# Kay_Tremolo.net
KiCad netlist of a schematic drawn in Altium Designer
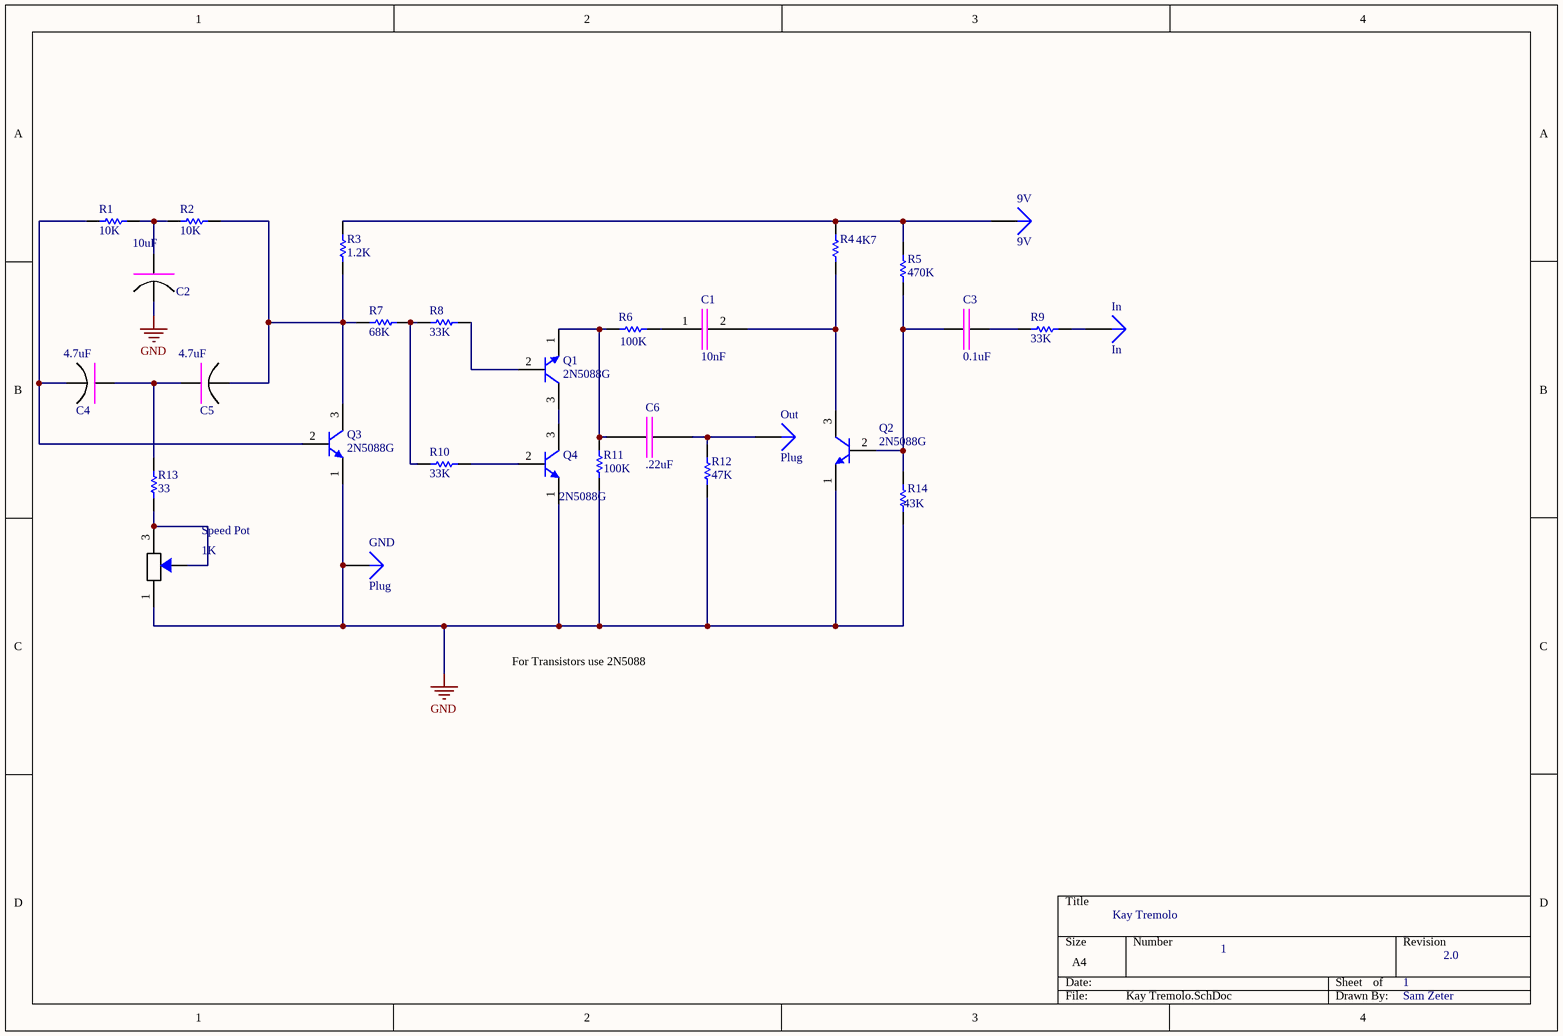
[diagram p0: Kay Tremolo.SchDoc]

(export (version "E")
  (design (tool "Eeschema 10.0.6"))
  (components
    (comp (ref "9V")
      (value "9V")
      (footprint "PIN1")
      (description "Plug")
      (fields (field (name "PUBLISHER") "Altium Limited"))
      (libsource (lib "Miscellaneous Connectors") (part "Plug"))
    )
    (comp (ref "C1")
      (value "10nF")
      (footprint "CapCer 2.5")
      (description "Ceramic Capactiro 2.5mm spaced leads")
      (libsource (lib "ZETER_Sch_Lib") (part "CapCer 2.5mm"))
    )
    (comp (ref "C2")
      (value "10uF")
      (footprint "CapElec 2")
      (description "2mm Lead Spaced Electro Cap")
      (libsource (lib "ZETER_Sch_Lib") (part "CapElec 2mm"))
    )
    (comp (ref "C3")
      (value "0.1uF")
      (footprint "CapCer 5")
      (description "5mm Spaced Ceramic Capacitor Leads")
      (libsource (lib "ZETER_Sch_Lib") (part "CapCer 5mm"))
    )
    (comp (ref "C4")
      (value "4.7uF")
      (footprint "CapElec 2")
      (description "2mm Lead Spaced Electro Cap")
      (libsource (lib "ZETER_Sch_Lib") (part "CapElec 2mm"))
    )
    (comp (ref "C5")
      (value "4.7uF")
      (footprint "CapElec 2")
      (description "2mm Lead Spaced Electro Cap")
      (libsource (lib "ZETER_Sch_Lib") (part "CapElec 2mm"))
    )
    (comp (ref "C6")
      (value ".22uF")
      (footprint "CapCer 5")
      (description "5mm Spaced Ceramic Capacitor Leads")
      (libsource (lib "") (part "CapCer 5mm_1"))
    )
    (comp (ref "GND")
      (value "Plug")
      (footprint "PIN1")
      (fields (field (name "PUBLISHER") "Altium Limited"))
      (libsource (lib "Miscellaneous Connectors") (part "Plug"))
    )
    (comp (ref "In")
      (value "In")
      (footprint "PIN1")
      (description "Plug")
      (fields (field (name "PUBLISHER") "Altium Limited"))
      (libsource (lib "Miscellaneous Connectors") (part "Plug"))
    )
    (comp (ref "Out")
      (value "Plug")
      (footprint "PIN1")
      (fields (field (name "PUBLISHER") "Altium Limited"))
      (libsource (lib "Miscellaneous Connectors") (part "Plug"))
    )
    (comp (ref "Q1")
      (value "2N5088G")
      (footprint "ONSC-TO-92-3-29-11")
      (description "Amplifier Transistor, NPN Silicon, 3-Pin TO-92, Pb-Free, Bulk Box")
      (fields (field (name "MANUFACTURER") "On Semiconductor"))
      (libsource (lib "ON Semi General Purpose Transistors") (part "2N5088G"))
    )
    (comp (ref "Q2")
      (value "2N5088G")
      (footprint "ONSC-TO-92-3-29-11")
      (description "Amplifier Transistor, NPN Silicon, 3-Pin TO-92, Pb-Free, Bulk Box")
      (fields (field (name "MANUFACTURER") "On Semiconductor"))
      (libsource (lib "ON Semi General Purpose Transistors") (part "2N5088G"))
    )
    (comp (ref "Q3")
      (value "2N5088G")
      (footprint "ONSC-TO-92-3-29-11")
      (description "Amplifier Transistor, NPN Silicon, 3-Pin TO-92, Pb-Free, Bulk Box")
      (fields (field (name "MANUFACTURER") "On Semiconductor"))
      (libsource (lib "ON Semi General Purpose Transistors") (part "2N5088G"))
    )
    (comp (ref "Q4")
      (value "2N5088G")
      (footprint "ONSC-TO-92-3-29-11")
      (description "Amplifier Transistor, NPN Silicon, 3-Pin TO-92, Pb-Free, Bulk Box")
      (fields (field (name "MANUFACTURER") "On Semiconductor"))
      (libsource (lib "ON Semi General Purpose Transistors") (part "2N5088G"))
    )
    (comp (ref "R1")
      (value "10K")
      (footprint "Axial 0.4")
      (description "TH Resistor 1/4 WATT")
      (fields (field (name "PUBLISHER") "Altium Limited"))
      (libsource (lib "ZETER_Sch_Lib") (part "Res 0.4"))
    )
    (comp (ref "R2")
      (value "10K")
      (footprint "Axial 0.4")
      (description "TH Resistor 1/4 WATT")
      (fields (field (name "PUBLISHER") "Altium Limited"))
      (libsource (lib "ZETER_Sch_Lib") (part "Res 0.4"))
    )
    (comp (ref "R3")
      (value "1.2K")
      (footprint "Axial 0.4")
      (description "TH Resistor 1/4 WATT")
      (fields (field (name "PUBLISHER") "Altium Limited"))
      (libsource (lib "ZETER_Sch_Lib") (part "Res 0.4"))
    )
    (comp (ref "R4")
      (value "4K7")
      (footprint "Axial 0.4")
      (description "TH Resistor 1/4 WATT")
      (fields (field (name "PUBLISHER") "Altium Limited"))
      (libsource (lib "ZETER_Sch_Lib") (part "Res 0.4"))
    )
    (comp (ref "R5")
      (value "470K")
      (footprint "Axial 0.4")
      (description "TH Resistor 1/4 WATT")
      (fields (field (name "PUBLISHER") "Altium Limited"))
      (libsource (lib "ZETER_Sch_Lib") (part "Res 0.4"))
    )
    (comp (ref "R6")
      (value "100K")
      (footprint "Axial 0.4")
      (description "TH Resistor 1/4 WATT")
      (fields (field (name "PUBLISHER") "Altium Limited"))
      (libsource (lib "ZETER_Sch_Lib") (part "Res 0.4"))
    )
    (comp (ref "R7")
      (value "68K")
      (footprint "Axial 0.4")
      (description "TH Resistor 1/4 WATT")
      (fields (field (name "PUBLISHER") "Altium Limited"))
      (libsource (lib "ZETER_Sch_Lib") (part "Res 0.4"))
    )
    (comp (ref "R8")
      (value "33K")
      (footprint "Axial 0.4")
      (description "TH Resistor 1/4 WATT")
      (fields (field (name "PUBLISHER") "Altium Limited"))
      (libsource (lib "ZETER_Sch_Lib") (part "Res 0.4"))
    )
    (comp (ref "R9")
      (value "33K")
      (footprint "Axial 0.4")
      (description "TH Resistor 1/4 WATT")
      (fields (field (name "PUBLISHER") "Altium Limited"))
      (libsource (lib "ZETER_Sch_Lib") (part "Res 0.4"))
    )
    (comp (ref "R10")
      (value "33K")
      (footprint "Axial 0.4")
      (description "TH Resistor 1/4 WATT")
      (fields (field (name "PUBLISHER") "Altium Limited"))
      (libsource (lib "ZETER_Sch_Lib") (part "Res 0.4"))
    )
    (comp (ref "R11")
      (value "100K")
      (footprint "Axial 0.4")
      (description "TH Resistor 1/4 WATT")
      (fields (field (name "PUBLISHER") "Altium Limited"))
      (libsource (lib "ZETER_Sch_Lib") (part "Res 0.4"))
    )
    (comp (ref "R12")
      (value "47K")
      (footprint "Axial 0.4")
      (description "TH Resistor 1/4 WATT")
      (fields (field (name "PUBLISHER") "Altium Limited"))
      (libsource (lib "ZETER_Sch_Lib") (part "Res 0.4"))
    )
    (comp (ref "R13")
      (value "33")
      (footprint "Axial 0.4")
      (description "TH Resistor 1/4 WATT")
      (fields (field (name "PUBLISHER") "Altium Limited"))
      (libsource (lib "ZETER_Sch_Lib") (part "Res 0.4"))
    )
    (comp (ref "R14")
      (value "43K")
      (footprint "Axial 0.4")
      (description "TH Resistor 1/4 WATT")
      (fields (field (name "PUBLISHER") "Altium Limited"))
      (libsource (lib "ZETER_Sch_Lib") (part "Res 0.4"))
    )
    (comp (ref "Speed Pot")
      (value "1K")
      (footprint "Potentiometer")
      (description "My Own")
      (libsource (lib "ZETER_Sch_Lib") (part "Potentiometer_1"))
    )
  )
  (nets
    (net (code "1") (name "GND") (class "Default")
      (node (ref "C2") (pin "2") (pinfunction "2_2") (pintype "passive"))
      (node (ref "GND") (pin "1") (pinfunction "1_1") (pintype "passive"))
      (node (ref "Q2") (pin "1") (pinfunction "E_1") (pintype "passive"))
      (node (ref "Q3") (pin "1") (pinfunction "E_1") (pintype "passive"))
      (node (ref "Q4") (pin "1") (pinfunction "E_1") (pintype "passive"))
      (node (ref "R11") (pin "1") (pinfunction "1_1") (pintype "passive"))
      (node (ref "R12") (pin "1") (pinfunction "1_1") (pintype "passive"))
      (node (ref "R14") (pin "1") (pinfunction "1_1") (pintype "passive"))
      (node (ref "Speed Pot") (pin "1") (pinfunction "1_1") (pintype "passive"))
    )
    (net (code "2") (name "Net-(9V-Pad1)") (class "Default")
      (node (ref "9V") (pin "1") (pinfunction "1_1") (pintype "passive"))
      (node (ref "R3") (pin "2") (pinfunction "2_2") (pintype "passive"))
      (node (ref "R4") (pin "1") (pinfunction "1_1") (pintype "passive"))
      (node (ref "R5") (pin "1") (pinfunction "1_1") (pintype "passive"))
    )
    (net (code "3") (name "Net-(C1-Pad1)") (class "Default")
      (node (ref "C1") (pin "1") (pinfunction "1_1") (pintype "passive"))
      (node (ref "R6") (pin "2") (pinfunction "2_2") (pintype "passive"))
    )
    (net (code "4") (name "Net-(C2-Pad1)") (class "Default")
      (node (ref "C2") (pin "1") (pinfunction "1_1") (pintype "passive"))
      (node (ref "R1") (pin "2") (pinfunction "2_2") (pintype "passive"))
      (node (ref "R2") (pin "1") (pinfunction "1_1") (pintype "passive"))
    )
    (net (code "5") (name "Net-(C3-Pad2)") (class "Default")
      (node (ref "C3") (pin "2") (pinfunction "2_2") (pintype "passive"))
      (node (ref "R9") (pin "2") (pinfunction "2_2") (pintype "passive"))
    )
    (net (code "6") (name "Net-(C4-Pad1)") (class "Default")
      (node (ref "C4") (pin "1") (pinfunction "1_1") (pintype "passive"))
      (node (ref "C5") (pin "1") (pinfunction "1_1") (pintype "passive"))
      (node (ref "R13") (pin "1") (pinfunction "1_1") (pintype "passive"))
    )
    (net (code "7") (name "Net-(C6-Pad2)") (class "Default")
      (node (ref "C6") (pin "2") (pinfunction "2_2") (pintype "passive"))
      (node (ref "Out") (pin "1") (pinfunction "1_1") (pintype "passive"))
      (node (ref "R12") (pin "2") (pinfunction "2_2") (pintype "passive"))
    )
    (net (code "8") (name "Net-(In-Pad1)") (class "Default")
      (node (ref "In") (pin "1") (pinfunction "1_1") (pintype "passive"))
      (node (ref "R9") (pin "1") (pinfunction "1_1") (pintype "passive"))
    )
    (net (code "9") (name "Net-(Q1-B)") (class "Default")
      (node (ref "Q1") (pin "2") (pinfunction "B_2") (pintype "passive"))
      (node (ref "R8") (pin "1") (pinfunction "1_1") (pintype "passive"))
    )
    (net (code "10") (name "Net-(Q1-C)") (class "Default")
      (node (ref "Q1") (pin "3") (pinfunction "C_3") (pintype "passive"))
      (node (ref "Q4") (pin "3") (pinfunction "C_3") (pintype "passive"))
    )
    (net (code "11") (name "Net-(Q1-E)") (class "Default")
      (node (ref "C6") (pin "1") (pinfunction "1_1") (pintype "passive"))
      (node (ref "Q1") (pin "1") (pinfunction "E_1") (pintype "passive"))
      (node (ref "R11") (pin "2") (pinfunction "2_2") (pintype "passive"))
      (node (ref "R6") (pin "1") (pinfunction "1_1") (pintype "passive"))
    )
    (net (code "12") (name "Net-(Q2-B)") (class "Default")
      (node (ref "C3") (pin "1") (pinfunction "1_1") (pintype "passive"))
      (node (ref "Q2") (pin "2") (pinfunction "B_2") (pintype "passive"))
      (node (ref "R14") (pin "2") (pinfunction "2_2") (pintype "passive"))
      (node (ref "R5") (pin "2") (pinfunction "2_2") (pintype "passive"))
    )
    (net (code "13") (name "Net-(Q2-C)") (class "Default")
      (node (ref "C1") (pin "2") (pinfunction "2_2") (pintype "passive"))
      (node (ref "Q2") (pin "3") (pinfunction "C_3") (pintype "passive"))
      (node (ref "R4") (pin "2") (pinfunction "2_2") (pintype "passive"))
    )
    (net (code "14") (name "Net-(Q3-B)") (class "Default")
      (node (ref "C4") (pin "2") (pinfunction "2_2") (pintype "passive"))
      (node (ref "Q3") (pin "2") (pinfunction "B_2") (pintype "passive"))
      (node (ref "R1") (pin "1") (pinfunction "1_1") (pintype "passive"))
    )
    (net (code "15") (name "Net-(Q3-C)") (class "Default")
      (node (ref "C5") (pin "2") (pinfunction "2_2") (pintype "passive"))
      (node (ref "Q3") (pin "3") (pinfunction "C_3") (pintype "passive"))
      (node (ref "R2") (pin "2") (pinfunction "2_2") (pintype "passive"))
      (node (ref "R3") (pin "1") (pinfunction "1_1") (pintype "passive"))
      (node (ref "R7") (pin "2") (pinfunction "2_2") (pintype "passive"))
    )
    (net (code "16") (name "Net-(Q4-B)") (class "Default")
      (node (ref "Q4") (pin "2") (pinfunction "B_2") (pintype "passive"))
      (node (ref "R10") (pin "1") (pinfunction "1_1") (pintype "passive"))
    )
    (net (code "17") (name "Net-(R10-Pad2)") (class "Default")
      (node (ref "R10") (pin "2") (pinfunction "2_2") (pintype "passive"))
      (node (ref "R7") (pin "1") (pinfunction "1_1") (pintype "passive"))
      (node (ref "R8") (pin "2") (pinfunction "2_2") (pintype "passive"))
    )
    (net (code "18") (name "Net-(R13-Pad2)") (class "Default")
      (node (ref "R13") (pin "2") (pinfunction "2_2") (pintype "passive"))
      (node (ref "Speed Pot") (pin "2") (pinfunction "2_2") (pintype "passive"))
      (node (ref "Speed Pot") (pin "3") (pinfunction "3_3") (pintype "passive"))
    )
  )
)
